# Power_Factor_Correction.net
KiCad netlist of a schematic drawn in Altium Designer
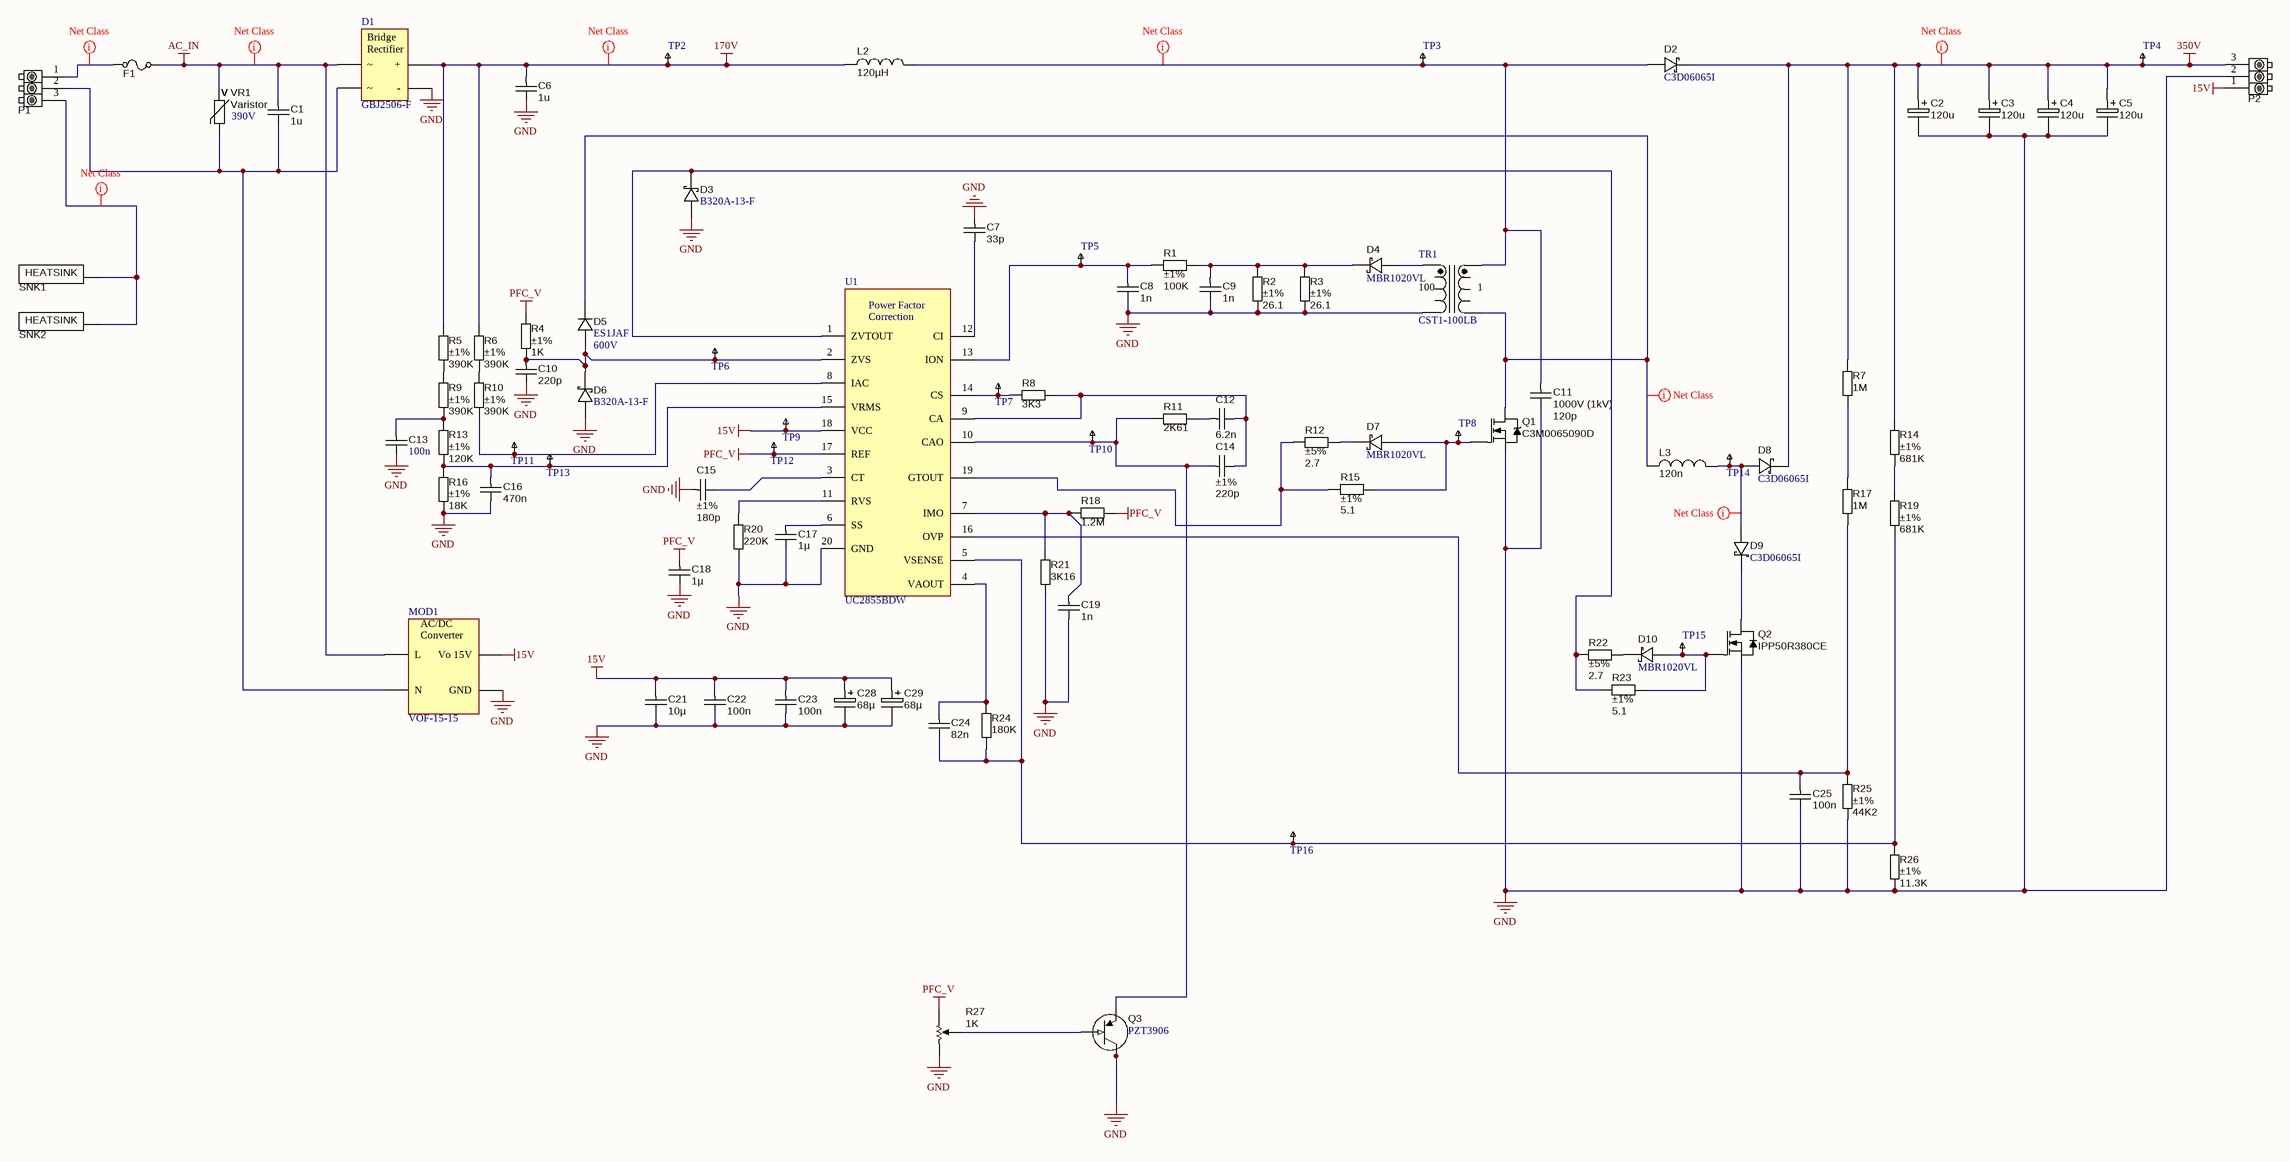
[diagram p0: Power Factor Correction.SchDoc]

(export (version "E")
  (design (tool "Eeschema 10.0.6"))
  (components
    (comp (ref "C1")
      (value "1u")
      (footprint "R71MI4100AA30K")
      (description "1µF Film Capacitor 220V 420V Polypropylene (PP), Metallized Radial")
      (fields (field (name "MANUFACTURER") "KEMET") (field (name "TOLERANCE") "±10%"))
      (libsource (lib "PBL - Capacitors") (part "CAPMF_1u_420V_MK"))
    )
    (comp (ref "C2")
      (value "120u")
      (footprint "Capacitor 22mmx25mm")
      (description "Aluminum Electrolytic Capacitors Radial, Can - Snap-In 2000 Hrs @ 85°C")
      (fields (field (name "MANUFACTURER") "United Chemi-Con") (field (name "TOLERANCE") "±20%"))
      (libsource (lib "PBL - Capacitors") (part "CAPE_120u_450V_THD"))
    )
    (comp (ref "C3")
      (value "120u")
      (footprint "Capacitor 22mmx25mm")
      (description "Aluminum Electrolytic Capacitors Radial, Can - Snap-In 2000 Hrs @ 85°C")
      (fields (field (name "MANUFACTURER") "United Chemi-Con") (field (name "TOLERANCE") "±20%"))
      (libsource (lib "PBL - Capacitors") (part "CAPE_120u_450V_THD"))
    )
    (comp (ref "C4")
      (value "120u")
      (footprint "Capacitor 22mmx25mm")
      (description "Aluminum Electrolytic Capacitors Radial, Can - Snap-In 2000 Hrs @ 85°C")
      (fields (field (name "MANUFACTURER") "United Chemi-Con") (field (name "TOLERANCE") "±20%"))
      (libsource (lib "PBL - Capacitors") (part "CAPE_120u_450V_THD"))
    )
    (comp (ref "C5")
      (value "120u")
      (footprint "Capacitor 22mmx25mm")
      (description "Aluminum Electrolytic Capacitors Radial, Can - Snap-In 2000 Hrs @ 85°C")
      (fields (field (name "MANUFACTURER") "United Chemi-Con") (field (name "TOLERANCE") "±20%"))
      (libsource (lib "PBL - Capacitors") (part "CAPE_120u_450V_THD"))
    )
    (comp (ref "C6")
      (value "1u")
      (footprint "R71MI4100AA30K")
      (description "1µF Film Capacitor 220V 420V Polypropylene (PP), Metallized Radial")
      (fields (field (name "MANUFACTURER") "KEMET") (field (name "TOLERANCE") "±10%"))
      (libsource (lib "PBL - Capacitors") (part "CAPMF_1u_420V_MK"))
    )
    (comp (ref "C7")
      (value "33p")
      (footprint "CAPC1608X90N")
      (description "Capacitor SMD Cer 33pF 5% 50V NP0 0603")
      (fields
        (field (name "TOLERANCE") "±5%")
        (field (name "MANUFACTURER") "Murata Electronics North America")
      )
      (libsource (lib "PBL - Capacitors") (part "CAPC_33p_0603_NP0_50V_5%"))
    )
    (comp (ref "C8")
      (value "1n")
      (footprint "CAPC1608X90N")
      (description "Capacitor SMD Cer 1nF 10% 100V X7R 0603")
      (fields (field (name "TOLERANCE") "±10%") (field (name "Comment") "approved sub OK"))
      (libsource (lib "PBL - Capacitors") (part "CAPC_1n_0603_X7R_100V_10%"))
    )
    (comp (ref "C9")
      (value "1n")
      (footprint "CAPC1608X90N")
      (description "Capacitor SMD Cer 1nF 10% 100V X7R 0603")
      (fields (field (name "TOLERANCE") "±10%") (field (name "Comment") "approved sub OK"))
      (libsource (lib "PBL - Capacitors") (part "CAPC_1n_0603_X7R_100V_10%"))
    )
    (comp (ref "C10")
      (value "220p")
      (footprint "CAPC1608X90N")
      (description "Capacitor SMD Cer 220pF 5% 50V NP0 0603")
      (fields (field (name "TOLERANCE") "±5%"))
      (libsource (lib "PBL - Capacitors") (part "CAPC_220p_0603_NP0_50V_5%"))
    )
    (comp (ref "C11")
      (value "120p")
      (footprint "CAPC3216X180N")
      (description "Capacitor SMD Cer 120pF 5% U2J 1KV 1206")
      (fields
        (field (name "TOLERANCE") "±5%")
        (field (name "MANUFACTURER") "Murata Electronics North America")
        (field (name "VOLTAGE - RATED") "1000V (1kV)")
      )
      (libsource (lib "PBL - Capacitors") (part "CAPC_120p_1206_U2J_1KV_5%"))
    )
    (comp (ref "C12")
      (value "6.2n")
      (footprint "CAPC1608X90N")
      (description "Capacitor SMD Cer 8pF ±0.5pF 50V NP0 0603")
      (fields
        (field (name "MANUFACTURER") "Murata Electronics North America")
        (field (name "TOLERANCE") "±5%")
      )
      (libsource (lib "PBL - Capacitors") (part "CAPC_6.2nF_0603_NP0_50V"))
    )
    (comp (ref "C13")
      (value "100n")
      (footprint "CAPC4532X280N")
      (description "0.1µF ±10% 630V Ceramic Capacitor X7R 1812 (4532 Metric)")
      (fields
        (field (name "MANUFACTURER") "Murata Electronics North America")
        (field (name "TOLERANCE") "±10%")
      )
      (libsource (lib "PBL - Capacitors") (part "CAPC_100n_1812_X7R_630V_10%"))
    )
    (comp (ref "C14")
      (value "220p")
      (footprint "CAPC1608X90N")
      (description "Capacitor SMD Cer 220pF 1% 50V NP0 0603")
      (fields (field (name "TOLERANCE") "±1%"))
      (libsource (lib "PBL - Capacitors") (part "CAPC_220p_0603_NP0_50V_1%"))
    )
    (comp (ref "C15")
      (value "180p")
      (footprint "CAPC1608X90N")
      (description "Capacitor SMD Cer 180pF 1% 50V NP0 0603")
      (fields (field (name "TOLERANCE") "±1%"))
      (libsource (lib "PBL - Capacitors") (part "CAPC_180p_0603_NP0_50V_1%"))
    )
    (comp (ref "C16")
      (value "470n")
      (footprint "CAPC2012X135N")
      (description "0.47µF ±10% 50V Ceramic Capacitor X7R 0805 (2012 Metric)")
      (fields
        (field (name "MANUFACTURER") "Murata Electronics North America")
        (field (name "TOLERANCE") "±10%")
      )
      (libsource (lib "PBL - Capacitors") (part "CAPC_470n_0805_X7R_50V_10%"))
    )
    (comp (ref "C17")
      (value "1µ")
      (footprint "CAPC3216X180N")
      (description "Capacitor SMD Cer 1uF 10% 35V X7R 1206")
      (fields (field (name "TOLERANCE") "±10%") (field (name "Comment") "approved sub OK"))
      (libsource (lib "PBL - Capacitors") (part "CAPC_1u_1206_X7R_35V_10%"))
    )
    (comp (ref "C18")
      (value "1µ")
      (footprint "CAPC3216X180N")
      (description "Capacitor SMD Cer 1uF 10% 35V X7R 1206")
      (fields (field (name "TOLERANCE") "±10%") (field (name "Comment") "approved sub OK"))
      (libsource (lib "PBL - Capacitors") (part "CAPC_1u_1206_X7R_35V_10%"))
    )
    (comp (ref "C19")
      (value "1n")
      (footprint "CAPC1608X90N")
      (description "Capacitor SMD Cer 1nF 10% 100V X7R 0603")
      (fields (field (name "TOLERANCE") "±10%") (field (name "Comment") "approved sub OK"))
      (libsource (lib "PBL - Capacitors") (part "CAPC_1n_0603_X7R_100V_10%"))
    )
    (comp (ref "C21")
      (value "10µ")
      (footprint "CAPC3225X220N")
      (description "Capacitor SMD Cer 10uF 20% 16V X5R 1210")
      (fields (field (name "TOLERANCE") "±20%"))
      (libsource (lib "PBL - Capacitors") (part "CAPC_10u_1210_50V"))
    )
    (comp (ref "C22")
      (value "100n")
      (footprint "CAPC2012X135N")
      (description "Capacitor SMD Cer 100nF 10% 50V X7R 0805")
      (fields (field (name "TOLERANCE") "±10%") (field (name "Comment") "approved sub OK"))
      (libsource (lib "PBL - Capacitors") (part "CAPC_100n_0805_X7R_50V_10%"))
    )
    (comp (ref "C23")
      (value "100n")
      (footprint "CAPC2012X135N")
      (description "Capacitor SMD Cer 100nF 10% 50V X7R 0805")
      (fields (field (name "TOLERANCE") "±10%") (field (name "Comment") "approved sub OK"))
      (libsource (lib "PBL - Capacitors") (part "CAPC_100n_0805_X7R_50V_10%"))
    )
    (comp (ref "C24")
      (value "82n")
      (footprint "CAPC1608X90N")
      (description "Capacitor SMD Cer 82nF 10% 50V X7R 0603")
      (fields
        (field (name "MANUFACTURER") "Murata Electronics North America")
        (field (name "TOLERANCE") "±10%")
      )
      (libsource (lib "PBL - Capacitors") (part "CAPC_82n_0603_X7R_50V_10%"))
    )
    (comp (ref "C25")
      (value "100n")
      (footprint "CAPC1608X90N")
      (description "Capacitor SMD Cer 100nF 10% 50V X7R 0603")
      (fields
        (field (name "TOLERANCE") "±10%")
        (field (name "MANUFACTURER") "Murata Electronics North America")
      )
      (libsource (lib "PBL - Capacitors") (part "CAPC_100n_0603_X7R_50V_10%"))
    )
    (comp (ref "C28")
      (value "68µ")
      (footprint "CAP_POLY_HXB_F80")
      (description "Capacitor SMD Alum Polymer 68uF 20% 35V")
      (fields (field (name "TOLERANCE") "±20%") (field (name "Comment") "HHXB350ARA680MF80G"))
      (libsource (lib "PBL - Capacitors") (part "CAPP_68u_35V_SMD"))
    )
    (comp (ref "C29")
      (value "68µ")
      (footprint "CAP_POLY_HXB_F80")
      (description "Capacitor SMD Alum Polymer 68uF 20% 35V")
      (fields (field (name "TOLERANCE") "±20%") (field (name "Comment") "HHXB350ARA680MF80G"))
      (libsource (lib "PBL - Capacitors") (part "CAPP_68u_35V_SMD"))
    )
    (comp (ref "D1")
      (value "GBJ2506-F")
      (footprint "4-SIP, GBJ")
      (description "Bridge Rectifier Single Phase 600V 25A Through Hole GBJ")
      (fields
        (field (name "MANUFACTURER") "Diodes Incorporated")
        (field (name "MANUFACTURER PART NUMBER") "GBJ2506-F")
      )
      (libsource (lib "PBL - Diodes") (part "BRIDGE_RECT_600V_25A_GBJ2506-F"))
    )
    (comp (ref "D2")
      (value "C3D06065I")
      (footprint "TO220-2")
      (description "Diode Silicon Carbide Schottky 13A (DC) Through Hole TO-220-2 Isolated Tab")
      (fields
        (field (name "MANUFACTURER") "Cree/Wolfspeed")
        (field (name "MANUFACTURER PART NUMBER") "C3D06065I")
      )
      (libsource (lib "PBL - Diodes") (part "DIODE_SIC_SCHOTTKY_650V_13A_C3D06065I"))
    )
    (comp (ref "D3")
      (value "B320A-13-F")
      (footprint "DO-214AC")
      (description "Diode Schottky 20V 3A Surface Mount SMA")
      (fields
        (field (name "MANUFACTURER") "Diodes Incorporated")
        (field (name "MANUFACTURER PART NUMBER") "B320A-13-F")
      )
      (libsource (lib "PBL - Diodes") (part "DIODE_SCHOTTKY_20V_3A_B320A-13-F"))
    )
    (comp (ref "D4")
      (value "B320A-13-F")
      (footprint "SOD123F")
      (description "Diode Schottky 20V 1A Surface Mount SOD-123F")
      (fields
        (field (name "MANUFACTURER") "Fairchild/ON Semiconductor")
        (field (name "MANUFACTURER PART NUMBER") "MBR1020VL")
      )
      (libsource (lib "PBL - Diodes") (part "DIODE_SCHOTTKY_20V_1A_MBR1020VL"))
    )
    (comp (ref "D5")
      (value "ES1JAF")
      (footprint "DO-214AD  SMAF")
      (description "Diode Standard 1A Surface Mount DO-214AD (SMAF)")
      (fields
        (field (name "MANUFACTURER") "Fairchild/ON Semiconductor")
        (field (name "MANUFACTURER PART NUMBER") "ES1JAF")
        (field (name "VOLTAGE - DC REVERSE (VR) (MAX)") "600V")
      )
      (libsource (lib "PBL - Diodes") (part "DIODE_600V_1A_SMA_ES1JAF"))
    )
    (comp (ref "D6")
      (value "B320A-13-F")
      (footprint "DO-214AC")
      (description "Diode Schottky 20V 3A Surface Mount SMA")
      (fields
        (field (name "MANUFACTURER") "Diodes Incorporated")
        (field (name "MANUFACTURER PART NUMBER") "B320A-13-F")
      )
      (libsource (lib "PBL - Diodes") (part "DIODE_SCHOTTKY_20V_3A_B320A-13-F"))
    )
    (comp (ref "D7")
      (value "B320A-13-F")
      (footprint "SOD123F")
      (description "Diode Schottky 20V 1A Surface Mount SOD-123F")
      (fields
        (field (name "MANUFACTURER") "Fairchild/ON Semiconductor")
        (field (name "MANUFACTURER PART NUMBER") "MBR1020VL")
      )
      (libsource (lib "PBL - Diodes") (part "DIODE_SCHOTTKY_20V_1A_MBR1020VL"))
    )
    (comp (ref "D8")
      (value "C3D06065I")
      (footprint "TO220-2")
      (description "Diode Silicon Carbide Schottky 13A (DC) Through Hole TO-220-2 Isolated Tab")
      (fields
        (field (name "MANUFACTURER") "Cree/Wolfspeed")
        (field (name "MANUFACTURER PART NUMBER") "C3D06065I")
      )
      (libsource (lib "PBL - Diodes") (part "DIODE_SIC_SCHOTTKY_650V_13A_C3D06065I"))
    )
    (comp (ref "D9")
      (value "C3D06065I")
      (footprint "TO220-2")
      (description "Diode Silicon Carbide Schottky 13A (DC) Through Hole TO-220-2 Isolated Tab")
      (fields
        (field (name "MANUFACTURER") "Cree/Wolfspeed")
        (field (name "MANUFACTURER PART NUMBER") "C3D06065I")
      )
      (libsource (lib "PBL - Diodes") (part "DIODE_SIC_SCHOTTKY_650V_13A_C3D06065I"))
    )
    (comp (ref "D10")
      (value "B320A-13-F")
      (footprint "SOD123F")
      (description "Diode Schottky 20V 1A Surface Mount SOD-123F")
      (fields
        (field (name "MANUFACTURER") "Fairchild/ON Semiconductor")
        (field (name "MANUFACTURER PART NUMBER") "MBR1020VL")
      )
      (libsource (lib "PBL - Diodes") (part "DIODE_SCHOTTKY_20V_1A_MBR1020VL"))
    )
    (comp (ref "F1")
      (value "Slow-blow")
      (footprint "3AB 3AG fuseholder")
      (description "Fuse Block 600V Circuit Cartridge PCB")
      (fields (field (name "MANUFACTURER") "Littelfuse Inc.") (field (name "VOLTAGE") "600V"))
      (libsource (lib "PBL - Fuses and Protection") (part "FUSE_HOLDER_   03540101ZXGY"))
    )
    (comp (ref "L2")
      (value "120µH")
      (footprint "ETD 44 Horizontal")
      (description "Custom Wound ETD44")
      (fields
        (field (name "TOLERANCE") "±10%")
        (field (name "BOBBIN MANUFACTURER PART NUMBER") "B66366B1018T001")
      )
      (libsource (lib "PBL - Inductors") (part "INDC_120u_ETD44_8A"))
    )
    (comp (ref "L3")
      (value "120n")
      (footprint "SLR1050")
      (description "Power Inductor 120nH 48.8A")
      (fields (field (name "TOLERANCE") "10±") (field (name "MANUFACTURER PART NUMBER") "SLR1050B-121KE_"))
      (libsource (lib "PBL - Inductors") (part "INDC_120n_48.8A"))
    )
    (comp (ref "MOD1")
      (value "VOF-15-15")
      (footprint "VOF-15-15 4 DIP")
      (description "Open Frame AC DC Converter 1 Output 15V 1A 85 ~ 264 VAC Input")
      (fields (field (name "MANUFACTURER") "CUI Inc.") (field (name "MANUFACTURER PART NUMBER") "VOF-15-15"))
      (libsource (lib "PBL - Power Supplies") (part "AC_DC_265V_15V_VOF-15-15"))
    )
    (comp (ref "P1")
      (value "*")
      (footprint "TE 796739-3 3 Screw Terminal")
      (description "3 Position Wire to Board Terminal Block Horizontal with Board 0.375\" (9.53mm) Through Hole")
      (fields (field (name "MANUFACTURER") "TE Connectivity AMP Connectors") (field (name "VOLTAGE") "600V"))
      (libsource (lib "PBL - Connectors") (part "3P_TERM BLOCK 796739-3"))
    )
    (comp (ref "P2")
      (value "*")
      (footprint "TE 796739-3 3 Screw Terminal")
      (description "3 Position Wire to Board Terminal Block Horizontal with Board 0.375\" (9.53mm) Through Hole")
      (fields (field (name "MANUFACTURER") "TE Connectivity AMP Connectors") (field (name "VOLTAGE") "600V"))
      (libsource (lib "") (part "3P_TERM BLOCK 796739-3_1"))
    )
    (comp (ref "Q1")
      (value "C3M0065090D")
      (footprint "TO-247-3")
      (description "N-Channel 36A (Tc) 125W (Tc) Through Hole TO-247-3")
      (fields (field (name "MANUFACTURER") "Cree/Wolfspeed"))
      (libsource (lib "PBL - Transistors") (part "SiC_N-CHAN_900V_36A_C3M0065090D"))
    )
    (comp (ref "Q2")
      (value "IPP50R380CE")
      (footprint "TO220V-GDS")
      (description "N-Channel 9.9A (Tc) 73W (Tc) Through Hole PG-TO-220-3")
      (fields (field (name "MANUFACTURER") "Infineon Technologies"))
      (libsource (lib "PBL - Transistors") (part "MOSFET_N-CHAN_IPP50R380CE"))
    )
    (comp (ref "Q3")
      (value "PNP")
      (footprint "SOT223")
      (description "Bipolar (BJT) Transistor PNP 40V 200mA 250MHz 1W Surface Mount SOT-223-4")
      (fields
        (field (name "MANUFACTURER") "ON Semiconductor")
        (field (name "MANUFACTURER PART NUMBER") "PZT3906")
      )
      (libsource (lib "PBL - Transistors") (part "PNP_PZT3906"))
    )
    (comp (ref "R1")
      (value "100K")
      (footprint "RESC1608X55N")
      (description "Resistor SMD chip 100k Ohm 0.1W 1% 0603")
      (fields (field (name "TOLERANCE") "±1%") (field (name "Comment") "Thick Film"))
      (libsource (lib "PBL - Resistors") (part "RES_100K_0603_1%"))
    )
    (comp (ref "R2")
      (value "26.1")
      (footprint "RESC2012X70N")
      (description "Resistor SMD chip 26.1k Ohm 0.125W 1% 0805")
      (fields
        (field (name "MANUFACTURER") "Panasonic Electronic Components")
        (field (name "TOLERANCE") "±1%")
        (field (name "MANUFACTURER PART NUMBER") "ERJ-6ENF26R1V")
      )
      (libsource (lib "PBL - Resistors") (part "RES_26R1_0805_1%"))
    )
    (comp (ref "R3")
      (value "26.1")
      (footprint "RESC2012X70N")
      (description "Resistor SMD chip 26.1k Ohm 0.125W 1% 0805")
      (fields
        (field (name "MANUFACTURER") "Panasonic Electronic Components")
        (field (name "TOLERANCE") "±1%")
        (field (name "MANUFACTURER PART NUMBER") "ERJ-6ENF26R1V")
      )
      (libsource (lib "PBL - Resistors") (part "RES_26R1_0805_1%"))
    )
    (comp (ref "R4")
      (value "1K")
      (footprint "RESC1608X55N")
      (description "Resistor SMD chip 1k Ohm 0.1W 1% 0603")
      (fields (field (name "TOLERANCE") "±1%") (field (name "Comment") "Thick Film"))
      (libsource (lib "PBL - Resistors") (part "RES_1K_0603_1%"))
    )
    (comp (ref "R5")
      (value "390K")
      (footprint "RESC2012X70N")
      (description "Resistor SMD chip 390k Ohm 0.125W 1% 0805")
      (fields
        (field (name "MANUFACTURER") "Panasonic Electronic Components")
        (field (name "TOLERANCE") "±1%")
        (field (name "MANUFACTURER PART NUMBER") "ERJ-6GEYJ394V")
      )
      (libsource (lib "PBL - Resistors") (part "RES_390K_0805_1%"))
    )
    (comp (ref "R6")
      (value "390K")
      (footprint "RESC2012X70N")
      (description "Resistor SMD chip 390k Ohm 0.125W 1% 0805")
      (fields
        (field (name "MANUFACTURER") "Panasonic Electronic Components")
        (field (name "TOLERANCE") "±1%")
        (field (name "MANUFACTURER PART NUMBER") "ERJ-6GEYJ394V")
      )
      (libsource (lib "PBL - Resistors") (part "RES_390K_0805_1%"))
    )
    (comp (ref "R7")
      (value "1M")
      (footprint "RESC2012X70N")
      (description "Resistor SMD chip 1M Ohm 0.125W 1% 0805")
      (fields
        (field (name "TOLERANCE") "±1%")
        (field (name "MANUFACTURER") "Panasonic Electronic Components")
      )
      (libsource (lib "PBL - Resistors") (part "RES_1M_0805_1%"))
    )
    (comp (ref "R8")
      (value "3K3")
      (footprint "RESC1608X55N")
      (description "Resistor SMD chip 3.3k Ohm 0.1W 1% 0603")
      (fields (field (name "TOLERANCE") "±1%") (field (name "MANUFACTURER") "Yageo"))
      (libsource (lib "PBL - Resistors") (part "RES_3K3_0603_1%"))
    )
    (comp (ref "R9")
      (value "390K")
      (footprint "RESC2012X70N")
      (description "Resistor SMD chip 390k Ohm 0.125W 1% 0805")
      (fields
        (field (name "MANUFACTURER") "Panasonic Electronic Components")
        (field (name "TOLERANCE") "±1%")
        (field (name "MANUFACTURER PART NUMBER") "ERJ-6GEYJ394V")
      )
      (libsource (lib "PBL - Resistors") (part "RES_390K_0805_1%"))
    )
    (comp (ref "R10")
      (value "390K")
      (footprint "RESC2012X70N")
      (description "Resistor SMD chip 390k Ohm 0.125W 1% 0805")
      (fields
        (field (name "MANUFACTURER") "Panasonic Electronic Components")
        (field (name "TOLERANCE") "±1%")
        (field (name "MANUFACTURER PART NUMBER") "ERJ-6GEYJ394V")
      )
      (libsource (lib "PBL - Resistors") (part "RES_390K_0805_1%"))
    )
    (comp (ref "R11")
      (value "2K61")
      (footprint "RESC1608X55N")
      (description "Resistor SMD chip 2.61k Ohm 0.1W 1% 0603")
      (fields
        (field (name "MANUFACTURER") "Panasonic Electronic Components")
        (field (name "TOLERANCE") "±1%")
      )
      (libsource (lib "PBL - Resistors") (part "RES_2K61_0603_1%"))
    )
    (comp (ref "R12")
      (value "2.7")
      (footprint "RESC1608X55N")
      (description "Resistor SMD chip 2.7 Ohm 0.1W 5% 0603")
      (fields
        (field (name "MANUFACTURER") "Panasonic Electronic Components")
        (field (name "MANUFACTURER PART NUMBER") "ERJ-3GEYJ2R7V")
        (field (name "TOLERANCE") "±5%")
      )
      (libsource (lib "PBL - Resistors") (part "RES_2R7_0603_5%"))
    )
    (comp (ref "R13")
      (value "120K")
      (footprint "RESC1608X55N")
      (description "Resistor SMD chip 120K Ohm 0.1W 1% 0603")
      (fields
        (field (name "MANUFACTURER") "Panasonic Electronic Components")
        (field (name "MANUFACTURER PART NUMBER") "ERJ-PA3F1203V")
        (field (name "TOLERANCE") "±1%")
      )
      (libsource (lib "PBL - Resistors") (part "RES_120K_0603_1%"))
    )
    (comp (ref "R14")
      (value "681K")
      (footprint "RESC2012X70N")
      (description "Resistor SMD chip 681K Ohm 0.125W 1% 0805")
      (fields
        (field (name "MANUFACTURER") "Panasonic Electronic Components")
        (field (name "TOLERANCE") "±1%")
        (field (name "MANUFACTURER PART NUMBER") "ERJ-6ENF6813V")
      )
      (libsource (lib "PBL - Resistors") (part "RES_681K_0805_1%"))
    )
    (comp (ref "R15")
      (value "5.1")
      (footprint "RESC1608X55N")
      (description "Resistor SMD chip 5.1 Ohm 0.1W 1% 0603")
      (fields
        (field (name "MANUFACTURER") "Yageo")
        (field (name "MANUFACTURER PART NUMBER") "RC0603FR-075R1L")
        (field (name "TOLERANCE") "±1%")
      )
      (libsource (lib "PBL - Resistors") (part "RES_5R1_0603_1%"))
    )
    (comp (ref "R16")
      (value "18K")
      (footprint "RESC1608X55N")
      (description "Resistor SMD chip 18K Ohm 0.1W 1% 0603")
      (fields
        (field (name "MANUFACTURER") "Panasonic Electronic Components")
        (field (name "TOLERANCE") "±1%")
        (field (name "MANUFACTURER PART NUMBER") "ERJ-3EKF1802V")
      )
      (libsource (lib "PBL - Resistors") (part "RES_18K_0603_1%"))
    )
    (comp (ref "R17")
      (value "1M")
      (footprint "RESC2012X70N")
      (description "Resistor SMD chip 1M Ohm 0.125W 1% 0805")
      (fields
        (field (name "TOLERANCE") "±1%")
        (field (name "MANUFACTURER") "Panasonic Electronic Components")
      )
      (libsource (lib "PBL - Resistors") (part "RES_1M_0805_1%"))
    )
    (comp (ref "R18")
      (value "1.2M")
      (footprint "RESC1608X55N")
      (description "Resistor SMD chip 1.2M Ohm 0.1W 1% 0603")
      (fields
        (field (name "TOLERANCE") "±1%")
        (field (name "MANUFACTURER") "Panasonic Electronic Components")
      )
      (libsource (lib "PBL - Resistors") (part "RES_1.2M_0603_1%"))
    )
    (comp (ref "R19")
      (value "681K")
      (footprint "RESC2012X70N")
      (description "Resistor SMD chip 681K Ohm 0.125W 1% 0805")
      (fields
        (field (name "MANUFACTURER") "Panasonic Electronic Components")
        (field (name "TOLERANCE") "±1%")
        (field (name "MANUFACTURER PART NUMBER") "ERJ-6ENF6813V")
      )
      (libsource (lib "PBL - Resistors") (part "RES_681K_0805_1%"))
    )
    (comp (ref "R20")
      (value "220K")
      (footprint "RESC1608X55N")
      (description "Resistor SMD chip 220k Ohm 0.1W 1% 0603")
      (fields
        (field (name "MANUFACTURER") "Panasonic Electronic Components")
        (field (name "TOLERANCE") "±1%")
      )
      (libsource (lib "PBL - Resistors") (part "RES_220K_0603_1%"))
    )
    (comp (ref "R21")
      (value "3K16")
      (footprint "RESC1608X55N")
      (description "Resistor SMD chip 3.16k Ohm 0.1W 1% 0603")
      (fields
        (field (name "TOLERANCE") "±1%")
        (field (name "MANUFACTURER") "Panasonic Electronic Components")
      )
      (libsource (lib "PBL - Resistors") (part "RES_3K16_0603_1%"))
    )
    (comp (ref "R22")
      (value "2.7")
      (footprint "RESC1608X55N")
      (description "Resistor SMD chip 2.7 Ohm 0.1W 5% 0603")
      (fields
        (field (name "MANUFACTURER") "Panasonic Electronic Components")
        (field (name "MANUFACTURER PART NUMBER") "ERJ-3GEYJ2R7V")
        (field (name "TOLERANCE") "±5%")
      )
      (libsource (lib "PBL - Resistors") (part "RES_2R7_0603_5%"))
    )
    (comp (ref "R23")
      (value "5.1")
      (footprint "RESC1608X55N")
      (description "Resistor SMD chip 5.1 Ohm 0.1W 1% 0603")
      (fields
        (field (name "MANUFACTURER") "Yageo")
        (field (name "MANUFACTURER PART NUMBER") "RC0603FR-075R1L")
        (field (name "TOLERANCE") "±1%")
      )
      (libsource (lib "PBL - Resistors") (part "RES_5R1_0603_1%"))
    )
    (comp (ref "R24")
      (value "180K")
      (footprint "RESC1608X55N")
      (description "Resistor SMD chip 180K Ohm 0.1W 1% 0603")
      (fields
        (field (name "TOLERANCE") "±1%")
        (field (name "MANUFACTURER") "Panasonic Electronic Components")
      )
      (libsource (lib "PBL - Resistors") (part "RES_180K_0603_1%"))
    )
    (comp (ref "R25")
      (value "44K2")
      (footprint "RESC2012X70N")
      (description "Resistor SMD chip 44.2k Ohm 0.125W 1% 0805")
      (fields
        (field (name "MANUFACTURER") "Panasonic Electronic Components")
        (field (name "TOLERANCE") "±1%")
        (field (name "MANUFACTURER PART NUMBER") "ERJ-3EKF4422V")
      )
      (libsource (lib "PBL - Resistors") (part "RES_44K2_0805_1%"))
    )
    (comp (ref "R26")
      (value "11.3K")
      (footprint "RESC1608X55N")
      (description "Resistor SMD chip 11.3K Ohm 0.1W 1% 0603")
      (fields
        (field (name "MANUFACTURER") "Panasonic Electronic Components")
        (field (name "MANUFACTURER PART NUMBER") "ERJ-3EKF1132V")
        (field (name "TOLERANCE") "±1%")
      )
      (libsource (lib "PBL - Resistors") (part "RES_11K3_0603_1%"))
    )
    (comp (ref "R27")
      (value "1K")
      (footprint "TrimPot_THT_2.54mm pitch")
      (description "Trimmer, 25-Turn, 1K cermet")
      (fields (field (name "TOLERANCE") "10%") (field (name "Comment") "25 Turn"))
      (libsource (lib "PBL - Resistors") (part "RES_TRIMMER_1K_25T_THT"))
    )
    (comp (ref "SNK1")
      (value "OMNI-UNI-41-75")
      (footprint "OMNI-UNI-41-75")
      (description "Heat Sink TO-247, TO-264 Aluminum Board Level, Vertical")
      (fields (field (name "MANUFACTURER") "Wakefield-Vette"))
      (libsource (lib "PBL - Mechanical") (part "HEATSINK_OMNI-UNI-41-75"))
    )
    (comp (ref "SNK2")
      (value "C247-025-1AE")
      (footprint "TO-247-2 With HeatSink 25mm")
      (description "Heat Sink TO-247 Aluminum 5W @ 60°C Board Level, Vertical")
      (fields (field (name "MANUFACTURER") "Ohmite"))
      (libsource (lib "PBL - Mechanical") (part "HEATSINK_C247-025-1AE"))
    )
    (comp (ref "TP2")
      (value "*")
      (footprint "1206 Test Point")
      (fields
        (field (name "MANUFACTURER") "TE Connectivity AMP Connectors")
        (field (name "MANUFACTURER PART NUMBER") "RCS-0C")
      )
      (libsource (lib "PBL - Test Points") (part "TESTPOINT SMD 1206"))
    )
    (comp (ref "TP3")
      (value "*")
      (footprint "1206 Test Point")
      (fields
        (field (name "MANUFACTURER") "TE Connectivity AMP Connectors")
        (field (name "MANUFACTURER PART NUMBER") "RCS-0C")
      )
      (libsource (lib "PBL - Test Points") (part "TESTPOINT SMD 1206"))
    )
    (comp (ref "TP4")
      (value "*")
      (footprint "1206 Test Point")
      (fields
        (field (name "MANUFACTURER") "TE Connectivity AMP Connectors")
        (field (name "MANUFACTURER PART NUMBER") "RCS-0C")
      )
      (libsource (lib "PBL - Test Points") (part "TESTPOINT SMD 1206"))
    )
    (comp (ref "TP5")
      (value "*")
      (footprint "1206 Test Point")
      (fields
        (field (name "MANUFACTURER") "TE Connectivity AMP Connectors")
        (field (name "MANUFACTURER PART NUMBER") "RCS-0C")
      )
      (libsource (lib "PBL - Test Points") (part "TESTPOINT SMD 1206"))
    )
    (comp (ref "TP6")
      (value "*")
      (footprint "1206 Test Point")
      (fields
        (field (name "MANUFACTURER") "TE Connectivity AMP Connectors")
        (field (name "MANUFACTURER PART NUMBER") "RCS-0C")
      )
      (libsource (lib "PBL - Test Points") (part "TESTPOINT SMD 1206"))
    )
    (comp (ref "TP7")
      (value "*")
      (footprint "1206 Test Point")
      (fields
        (field (name "MANUFACTURER") "TE Connectivity AMP Connectors")
        (field (name "MANUFACTURER PART NUMBER") "RCS-0C")
      )
      (libsource (lib "PBL - Test Points") (part "TESTPOINT SMD 1206"))
    )
    (comp (ref "TP8")
      (value "*")
      (footprint "1206 Test Point")
      (fields
        (field (name "MANUFACTURER") "TE Connectivity AMP Connectors")
        (field (name "MANUFACTURER PART NUMBER") "RCS-0C")
      )
      (libsource (lib "PBL - Test Points") (part "TESTPOINT SMD 1206"))
    )
    (comp (ref "TP9")
      (value "*")
      (footprint "1206 Test Point")
      (fields
        (field (name "MANUFACTURER") "TE Connectivity AMP Connectors")
        (field (name "MANUFACTURER PART NUMBER") "RCS-0C")
      )
      (libsource (lib "PBL - Test Points") (part "TESTPOINT SMD 1206"))
    )
    (comp (ref "TP10")
      (value "*")
      (footprint "1206 Test Point")
      (fields
        (field (name "MANUFACTURER") "TE Connectivity AMP Connectors")
        (field (name "MANUFACTURER PART NUMBER") "RCS-0C")
      )
      (libsource (lib "PBL - Test Points") (part "TESTPOINT SMD 1206"))
    )
    (comp (ref "TP11")
      (value "*")
      (footprint "1206 Test Point")
      (fields
        (field (name "MANUFACTURER") "TE Connectivity AMP Connectors")
        (field (name "MANUFACTURER PART NUMBER") "RCS-0C")
      )
      (libsource (lib "PBL - Test Points") (part "TESTPOINT SMD 1206"))
    )
    (comp (ref "TP12")
      (value "*")
      (footprint "1206 Test Point")
      (fields
        (field (name "MANUFACTURER") "TE Connectivity AMP Connectors")
        (field (name "MANUFACTURER PART NUMBER") "RCS-0C")
      )
      (libsource (lib "PBL - Test Points") (part "TESTPOINT SMD 1206"))
    )
    (comp (ref "TP13")
      (value "*")
      (footprint "1206 Test Point")
      (fields
        (field (name "MANUFACTURER") "TE Connectivity AMP Connectors")
        (field (name "MANUFACTURER PART NUMBER") "RCS-0C")
      )
      (libsource (lib "PBL - Test Points") (part "TESTPOINT SMD 1206"))
    )
    (comp (ref "TP14")
      (value "*")
      (footprint "1206 Test Point")
      (fields
        (field (name "MANUFACTURER") "TE Connectivity AMP Connectors")
        (field (name "MANUFACTURER PART NUMBER") "RCS-0C")
      )
      (libsource (lib "PBL - Test Points") (part "TESTPOINT SMD 1206"))
    )
    (comp (ref "TP15")
      (value "*")
      (footprint "1206 Test Point")
      (fields
        (field (name "MANUFACTURER") "TE Connectivity AMP Connectors")
        (field (name "MANUFACTURER PART NUMBER") "RCS-0C")
      )
      (libsource (lib "PBL - Test Points") (part "TESTPOINT SMD 1206"))
    )
    (comp (ref "TP16")
      (value "*")
      (footprint "1206 Test Point")
      (fields
        (field (name "MANUFACTURER") "TE Connectivity AMP Connectors")
        (field (name "MANUFACTURER PART NUMBER") "RCS-0C")
      )
      (libsource (lib "PBL - Test Points") (part "TESTPOINT SMD 1206"))
    )
    (comp (ref "TR1")
      (value "CST1-100LB")
      (footprint "CST1")
      (description "Sufrace Mount Current Transformer 100:1 Ratio 20A")
      (libsource (lib "PBL - Transformers") (part "CURRENT_100{colon}1_20A_CST1-100LB"))
    )
    (comp (ref "U1")
      (value "UC2855ADW")
      (footprint "SOIC127P1030X265-20N")
      (description "PFC IC Average Current 500kHz 20-SOIC")
      (fields
        (field (name "MANUFACTURER") "Texas Instruments")
        (field (name "MANUFACTURER PART NUMBER") "UC2855BDW")
      )
      (libsource (lib "PBL - Regulators") (part "PFC_UC2855BDW"))
    )
    (comp (ref "VR1")
      (value "Varistor")
      (footprint "B722 14MM MOV")
      (description "390V Varistor Circuit Through Hole Disc 14mm")
      (fields
        (field (name "MANUFACTURER") "EPCOS (TDK)")
        (field (name "VARISTOR VOLTAGE (TYP)") "390V")
        (field (name "MANUFACTURER PART NUMBER") "B72214S0251K101")
      )
      (libsource (lib "PBL - Fuses and Protection") (part "Varistor_390V_4.5KA_B72214S0251K101"))
    )
  )
  (nets
    (net (code "1") (name "15V") (class "Default")
      (node (ref "C21") (pin "1") (pintype "passive"))
      (node (ref "C22") (pin "1") (pintype "passive"))
      (node (ref "C23") (pin "1") (pintype "passive"))
      (node (ref "C28") (pin "1") (pintype "passive"))
      (node (ref "C29") (pin "1") (pintype "passive"))
      (node (ref "MOD1") (pin "Vo") (pinfunction "Vo_15V_Vo") (pintype "passive"))
      (node (ref "P2") (pin "1") (pinfunction "1_1") (pintype "passive"))
      (node (ref "TP9") (pin "1") (pintype "passive"))
      (node (ref "U1") (pin "18") (pinfunction "VCC_18") (pintype "passive"))
    )
    (net (code "2") (name "170V") (class "Default")
      (node (ref "C6") (pin "1") (pintype "passive"))
      (node (ref "D1") (pin "1") (pinfunction "+_1") (pintype "passive"))
      (node (ref "L2") (pin "1") (pinfunction "1_1") (pintype "passive"))
      (node (ref "R5") (pin "1") (pinfunction "1_1") (pintype "passive"))
      (node (ref "R6") (pin "1") (pinfunction "1_1") (pintype "passive"))
      (node (ref "TP2") (pin "1") (pintype "passive"))
    )
    (net (code "3") (name "350V") (class "Default")
      (node (ref "C2") (pin "1") (pintype "passive"))
      (node (ref "C3") (pin "1") (pintype "passive"))
      (node (ref "C4") (pin "1") (pintype "passive"))
      (node (ref "C5") (pin "1") (pintype "passive"))
      (node (ref "D2") (pin "1") (pinfunction "K_1") (pintype "passive"))
      (node (ref "D8") (pin "1") (pinfunction "K_1") (pintype "passive"))
      (node (ref "P2") (pin "3") (pinfunction "3_3") (pintype "passive"))
      (node (ref "R14") (pin "1") (pinfunction "1_1") (pintype "passive"))
      (node (ref "R7") (pin "1") (pinfunction "1_1") (pintype "passive"))
      (node (ref "TP4") (pin "1") (pintype "passive"))
    )
    (net (code "4") (name "AC_IN") (class "Default")
      (node (ref "C1") (pin "1") (pintype "passive"))
      (node (ref "D1") (pin "2") (pinfunction "~_2") (pintype "passive"))
      (node (ref "F1") (pin "2") (pinfunction "2_2") (pintype "passive"))
      (node (ref "MOD1") (pin "L") (pinfunction "L_L") (pintype "passive"))
      (node (ref "VR1") (pin "1") (pinfunction "1_1") (pintype "passive"))
    )
    (net (code "5") (name "GND") (class "Default")
      (node (ref "C10") (pin "2") (pintype "passive"))
      (node (ref "C11") (pin "2") (pintype "passive"))
      (node (ref "C13") (pin "2") (pintype "passive"))
      (node (ref "C15") (pin "1") (pintype "passive"))
      (node (ref "C16") (pin "2") (pintype "passive"))
      (node (ref "C17") (pin "2") (pintype "passive"))
      (node (ref "C18") (pin "2") (pintype "passive"))
      (node (ref "C19") (pin "2") (pintype "passive"))
      (node (ref "C2") (pin "2") (pintype "passive"))
      (node (ref "C21") (pin "2") (pintype "passive"))
      (node (ref "C22") (pin "2") (pintype "passive"))
      (node (ref "C23") (pin "2") (pintype "passive"))
      (node (ref "C25") (pin "2") (pintype "passive"))
      (node (ref "C28") (pin "2") (pintype "passive"))
      (node (ref "C29") (pin "2") (pintype "passive"))
      (node (ref "C3") (pin "2") (pintype "passive"))
      (node (ref "C4") (pin "2") (pintype "passive"))
      (node (ref "C5") (pin "2") (pintype "passive"))
      (node (ref "C6") (pin "2") (pintype "passive"))
      (node (ref "C7") (pin "1") (pintype "passive"))
      (node (ref "C8") (pin "2") (pintype "passive"))
      (node (ref "C9") (pin "2") (pintype "passive"))
      (node (ref "D1") (pin "4") (pinfunction "-_4") (pintype "passive"))
      (node (ref "D3") (pin "A") (pinfunction "A_A") (pintype "passive"))
      (node (ref "D6") (pin "A") (pinfunction "A_A") (pintype "passive"))
      (node (ref "MOD1") (pin "GND") (pinfunction "GND_GND") (pintype "passive"))
      (node (ref "P2") (pin "2") (pinfunction "2_2") (pintype "passive"))
      (node (ref "Q1") (pin "3") (pinfunction "S_3") (pintype "passive"))
      (node (ref "Q2") (pin "3") (pinfunction "S_3") (pintype "passive"))
      (node (ref "Q3") (pin "2") (pinfunction "C_2") (pintype "passive"))
      (node (ref "Q3") (pin "4") (pinfunction "C_4") (pintype "passive"))
      (node (ref "R16") (pin "2") (pinfunction "2_2") (pintype "passive"))
      (node (ref "R2") (pin "2") (pinfunction "2_2") (pintype "passive"))
      (node (ref "R20") (pin "2") (pinfunction "2_2") (pintype "passive"))
      (node (ref "R21") (pin "2") (pinfunction "2_2") (pintype "passive"))
      (node (ref "R25") (pin "2") (pinfunction "2_2") (pintype "passive"))
      (node (ref "R26") (pin "2") (pinfunction "2_2") (pintype "passive"))
      (node (ref "R27") (pin "3") (pinfunction "CW_3") (pintype "passive"))
      (node (ref "R3") (pin "2") (pinfunction "2_2") (pintype "passive"))
      (node (ref "TR1") (pin "4") (pinfunction "4_4") (pintype "passive"))
      (node (ref "U1") (pin "20") (pinfunction "GND_20") (pintype "passive"))
    )
    (net (code "6") (name "Net-(C1-Pad2)") (class "Default")
      (node (ref "C1") (pin "2") (pintype "passive"))
      (node (ref "D1") (pin "3") (pinfunction "~_3") (pintype "passive"))
      (node (ref "MOD1") (pin "N") (pinfunction "N_N") (pintype "passive"))
      (node (ref "P1") (pin "2") (pinfunction "2_2") (pintype "passive"))
      (node (ref "VR1") (pin "2") (pinfunction "2_2") (pintype "passive"))
    )
    (net (code "7") (name "Net-(C9-Pad1)") (class "Default")
      (node (ref "C9") (pin "1") (pintype "passive"))
      (node (ref "D4") (pin "K") (pinfunction "K_K") (pintype "passive"))
      (node (ref "R1") (pin "2") (pinfunction "2_2") (pintype "passive"))
      (node (ref "R2") (pin "1") (pinfunction "1_1") (pintype "passive"))
      (node (ref "R3") (pin "1") (pinfunction "1_1") (pintype "passive"))
    )
    (net (code "8") (name "Net-(C12-Pad1)") (class "Default")
      (node (ref "C12") (pin "1") (pintype "passive"))
      (node (ref "R11") (pin "2") (pinfunction "2_2") (pintype "passive"))
    )
    (net (code "9") (name "Net-(C13-Pad1)") (class "Default")
      (node (ref "C13") (pin "1") (pintype "passive"))
      (node (ref "R13") (pin "1") (pinfunction "1_1") (pintype "passive"))
      (node (ref "R9") (pin "2") (pinfunction "2_2") (pintype "passive"))
    )
    (net (code "10") (name "Net-(D2-A)") (class "Default")
      (node (ref "C11") (pin "1") (pintype "passive"))
      (node (ref "D2") (pin "2") (pinfunction "A_2") (pintype "passive"))
      (node (ref "L2") (pin "2") (pinfunction "2_2") (pintype "passive"))
      (node (ref "TP3") (pin "1") (pintype "passive"))
      (node (ref "TR1") (pin "8") (pinfunction "8_8") (pintype "passive"))
    )
    (net (code "11") (name "Net-(D4-PadA)") (class "Default")
      (node (ref "D4") (pin "A") (pinfunction "A_A") (pintype "passive"))
      (node (ref "TR1") (pin "6") (pinfunction "6_6") (pintype "passive"))
    )
    (net (code "12") (name "Net-(D7-PadK)") (class "Default")
      (node (ref "D7") (pin "K") (pinfunction "K_K") (pintype "passive"))
      (node (ref "R12") (pin "2") (pinfunction "2_2") (pintype "passive"))
    )
    (net (code "13") (name "Net-(D8-A)") (class "Default")
      (node (ref "D8") (pin "2") (pinfunction "A_2") (pintype "passive"))
      (node (ref "D9") (pin "2") (pinfunction "A_2") (pintype "passive"))
      (node (ref "L3") (pin "2") (pinfunction "2_2") (pintype "passive"))
      (node (ref "TP14") (pin "1") (pintype "passive"))
    )
    (net (code "14") (name "Net-(D9-K)") (class "Default")
      (node (ref "D9") (pin "1") (pinfunction "K_1") (pintype "passive"))
      (node (ref "Q2") (pin "2") (pinfunction "D_2") (pintype "passive"))
    )
    (net (code "15") (name "Net-(D10-PadK)") (class "Default")
      (node (ref "D10") (pin "K") (pinfunction "K_K") (pintype "passive"))
      (node (ref "R22") (pin "2") (pinfunction "2_2") (pintype "passive"))
    )
    (net (code "16") (name "Net-(F1-Pad1)") (class "Default")
      (node (ref "F1") (pin "1") (pinfunction "1_1") (pintype "passive"))
      (node (ref "P1") (pin "1") (pinfunction "1_1") (pintype "passive"))
    )
    (net (code "17") (name "Net-(Q1-D)") (class "Default")
      (node (ref "D5") (pin "K") (pinfunction "K_K") (pintype "passive"))
      (node (ref "L3") (pin "1") (pinfunction "1_1") (pintype "passive"))
      (node (ref "Q1") (pin "2") (pinfunction "D_2") (pintype "passive"))
      (node (ref "TR1") (pin "7") (pinfunction "7_7") (pintype "passive"))
    )
    (net (code "18") (name "Net-(Q1-G)") (class "Default")
      (node (ref "D7") (pin "A") (pinfunction "A_A") (pintype "passive"))
      (node (ref "Q1") (pin "1") (pinfunction "G_1") (pintype "passive"))
      (node (ref "R15") (pin "2") (pinfunction "2_2") (pintype "passive"))
      (node (ref "TP8") (pin "1") (pintype "passive"))
    )
    (net (code "19") (name "Net-(Q2-G)") (class "Default")
      (node (ref "D10") (pin "A") (pinfunction "A_A") (pintype "passive"))
      (node (ref "Q2") (pin "1") (pinfunction "G_1") (pintype "passive"))
      (node (ref "R23") (pin "2") (pinfunction "2_2") (pintype "passive"))
      (node (ref "TP15") (pin "1") (pintype "passive"))
    )
    (net (code "20") (name "Net-(Q3-B)") (class "Default")
      (node (ref "Q3") (pin "1") (pinfunction "B_1") (pintype "input"))
      (node (ref "R27") (pin "2") (pinfunction "TAP_2") (pintype "passive"))
    )
    (net (code "21") (name "Net-(Q3-E)") (class "Default")
      (node (ref "C14") (pin "1") (pintype "passive"))
      (node (ref "Q3") (pin "3") (pinfunction "E_3") (pintype "passive"))
      (node (ref "R11") (pin "1") (pinfunction "1_1") (pintype "passive"))
      (node (ref "TP10") (pin "1") (pintype "passive"))
      (node (ref "U1") (pin "10") (pinfunction "CAO_10") (pintype "passive"))
    )
    (net (code "22") (name "Net-(R5-Pad2)") (class "Default")
      (node (ref "R5") (pin "2") (pinfunction "2_2") (pintype "passive"))
      (node (ref "R9") (pin "1") (pinfunction "1_1") (pintype "passive"))
    )
    (net (code "23") (name "Net-(R10-Pad1)") (class "Default")
      (node (ref "R10") (pin "1") (pinfunction "1_1") (pintype "passive"))
      (node (ref "R6") (pin "2") (pinfunction "2_2") (pintype "passive"))
    )
    (net (code "24") (name "Net-(R14-Pad2)") (class "Default")
      (node (ref "R14") (pin "2") (pinfunction "2_2") (pintype "passive"))
      (node (ref "R19") (pin "1") (pinfunction "1_1") (pintype "passive"))
    )
    (net (code "25") (name "Net-(R17-Pad1)") (class "Default")
      (node (ref "R17") (pin "1") (pinfunction "1_1") (pintype "passive"))
      (node (ref "R7") (pin "2") (pinfunction "2_2") (pintype "passive"))
    )
    (net (code "26") (name "Net-(SNK1-GND)") (class "Default")
      (node (ref "P1") (pin "3") (pinfunction "3_3") (pintype "passive"))
      (node (ref "SNK1") (pin "0") (pinfunction "GND_0") (pintype "passive"))
      (node (ref "SNK2") (pin "0") (pinfunction "GND_0") (pintype "passive"))
    )
    (net (code "27") (name "Net-(U1-CA)") (class "Default")
      (node (ref "C12") (pin "2") (pintype "passive"))
      (node (ref "C14") (pin "2") (pintype "passive"))
      (node (ref "R8") (pin "2") (pinfunction "2_2") (pintype "passive"))
      (node (ref "U1") (pin "9") (pinfunction "CA_9") (pintype "passive"))
    )
    (net (code "28") (name "Net-(U1-CI)") (class "Default")
      (node (ref "C7") (pin "2") (pintype "passive"))
      (node (ref "U1") (pin "12") (pinfunction "CI_12") (pintype "passive"))
    )
    (net (code "29") (name "Net-(U1-CS)") (class "Default")
      (node (ref "R8") (pin "1") (pinfunction "1_1") (pintype "passive"))
      (node (ref "TP7") (pin "1") (pintype "passive"))
      (node (ref "U1") (pin "14") (pinfunction "CS_14") (pintype "passive"))
    )
    (net (code "30") (name "Net-(U1-CT)") (class "Default")
      (node (ref "C15") (pin "2") (pintype "passive"))
      (node (ref "U1") (pin "3") (pinfunction "CT_3") (pintype "passive"))
    )
    (net (code "31") (name "Net-(U1-GTOUT)") (class "Default")
      (node (ref "R12") (pin "1") (pinfunction "1_1") (pintype "passive"))
      (node (ref "R15") (pin "1") (pinfunction "1_1") (pintype "passive"))
      (node (ref "U1") (pin "19") (pinfunction "GTOUT_19") (pintype "passive"))
    )
    (net (code "32") (name "Net-(U1-IAC)") (class "Default")
      (node (ref "R10") (pin "2") (pinfunction "2_2") (pintype "passive"))
      (node (ref "TP11") (pin "1") (pintype "passive"))
      (node (ref "U1") (pin "8") (pinfunction "IAC_8") (pintype "passive"))
    )
    (net (code "33") (name "Net-(U1-IMO)") (class "Default")
      (node (ref "C19") (pin "1") (pintype "passive"))
      (node (ref "R18") (pin "2") (pinfunction "2_2") (pintype "passive"))
      (node (ref "R21") (pin "1") (pinfunction "1_1") (pintype "passive"))
      (node (ref "U1") (pin "7") (pinfunction "IMO_7") (pintype "passive"))
    )
    (net (code "34") (name "Net-(U1-ION)") (class "Default")
      (node (ref "C8") (pin "1") (pintype "passive"))
      (node (ref "R1") (pin "1") (pinfunction "1_1") (pintype "passive"))
      (node (ref "TP5") (pin "1") (pintype "passive"))
      (node (ref "U1") (pin "13") (pinfunction "ION_13") (pintype "passive"))
    )
    (net (code "35") (name "Net-(U1-OVP)") (class "Default")
      (node (ref "C25") (pin "1") (pintype "passive"))
      (node (ref "R17") (pin "2") (pinfunction "2_2") (pintype "passive"))
      (node (ref "R25") (pin "1") (pinfunction "1_1") (pintype "passive"))
      (node (ref "U1") (pin "16") (pinfunction "OVP_16") (pintype "passive"))
    )
    (net (code "36") (name "Net-(U1-RVS)") (class "Default")
      (node (ref "R20") (pin "1") (pinfunction "1_1") (pintype "passive"))
      (node (ref "U1") (pin "11") (pinfunction "RVS_11") (pintype "passive"))
    )
    (net (code "37") (name "Net-(U1-SS)") (class "Default")
      (node (ref "C17") (pin "1") (pintype "passive"))
      (node (ref "U1") (pin "6") (pinfunction "SS_6") (pintype "passive"))
    )
    (net (code "38") (name "Net-(U1-VAOUT)") (class "Default")
      (node (ref "C24") (pin "1") (pintype "passive"))
      (node (ref "R24") (pin "1") (pinfunction "1_1") (pintype "passive"))
      (node (ref "U1") (pin "4") (pinfunction "VAOUT_4") (pintype "passive"))
    )
    (net (code "39") (name "Net-(U1-VRMS)") (class "Default")
      (node (ref "C16") (pin "1") (pintype "passive"))
      (node (ref "R13") (pin "2") (pinfunction "2_2") (pintype "passive"))
      (node (ref "R16") (pin "1") (pinfunction "1_1") (pintype "passive"))
      (node (ref "TP13") (pin "1") (pintype "passive"))
      (node (ref "U1") (pin "15") (pinfunction "VRMS_15") (pintype "passive"))
    )
    (net (code "40") (name "Net-(U1-VSENSE)") (class "Default")
      (node (ref "C24") (pin "2") (pintype "passive"))
      (node (ref "R19") (pin "2") (pinfunction "2_2") (pintype "passive"))
      (node (ref "R24") (pin "2") (pinfunction "2_2") (pintype "passive"))
      (node (ref "R26") (pin "1") (pinfunction "1_1") (pintype "passive"))
      (node (ref "TP16") (pin "1") (pintype "passive"))
      (node (ref "U1") (pin "5") (pinfunction "VSENSE_5") (pintype "passive"))
    )
    (net (code "41") (name "Net-(U1-ZVS)") (class "Default")
      (node (ref "C10") (pin "1") (pintype "passive"))
      (node (ref "D5") (pin "A") (pinfunction "A_A") (pintype "passive"))
      (node (ref "D6") (pin "K") (pinfunction "K_K") (pintype "passive"))
      (node (ref "R4") (pin "2") (pinfunction "2_2") (pintype "passive"))
      (node (ref "TP6") (pin "1") (pintype "passive"))
      (node (ref "U1") (pin "2") (pinfunction "ZVS_2") (pintype "passive"))
    )
    (net (code "42") (name "Net-(U1-ZVTOUT)") (class "Default")
      (node (ref "D3") (pin "K") (pinfunction "K_K") (pintype "passive"))
      (node (ref "R22") (pin "1") (pinfunction "1_1") (pintype "passive"))
      (node (ref "R23") (pin "1") (pinfunction "1_1") (pintype "passive"))
      (node (ref "U1") (pin "1") (pinfunction "ZVTOUT_1") (pintype "passive"))
    )
    (net (code "43") (name "PFC_V") (class "Default")
      (node (ref "C18") (pin "1") (pintype "passive"))
      (node (ref "R18") (pin "1") (pinfunction "1_1") (pintype "passive"))
      (node (ref "R27") (pin "1") (pinfunction "CCW_1") (pintype "passive"))
      (node (ref "R4") (pin "1") (pinfunction "1_1") (pintype "passive"))
      (node (ref "TP12") (pin "1") (pintype "passive"))
      (node (ref "U1") (pin "17") (pinfunction "REF_17") (pintype "passive"))
    )
  )
)
